# Sensor_Module_0x04_Luminosity_TSL2561_v2.net
KiCad netlist of a schematic drawn in EAGLE
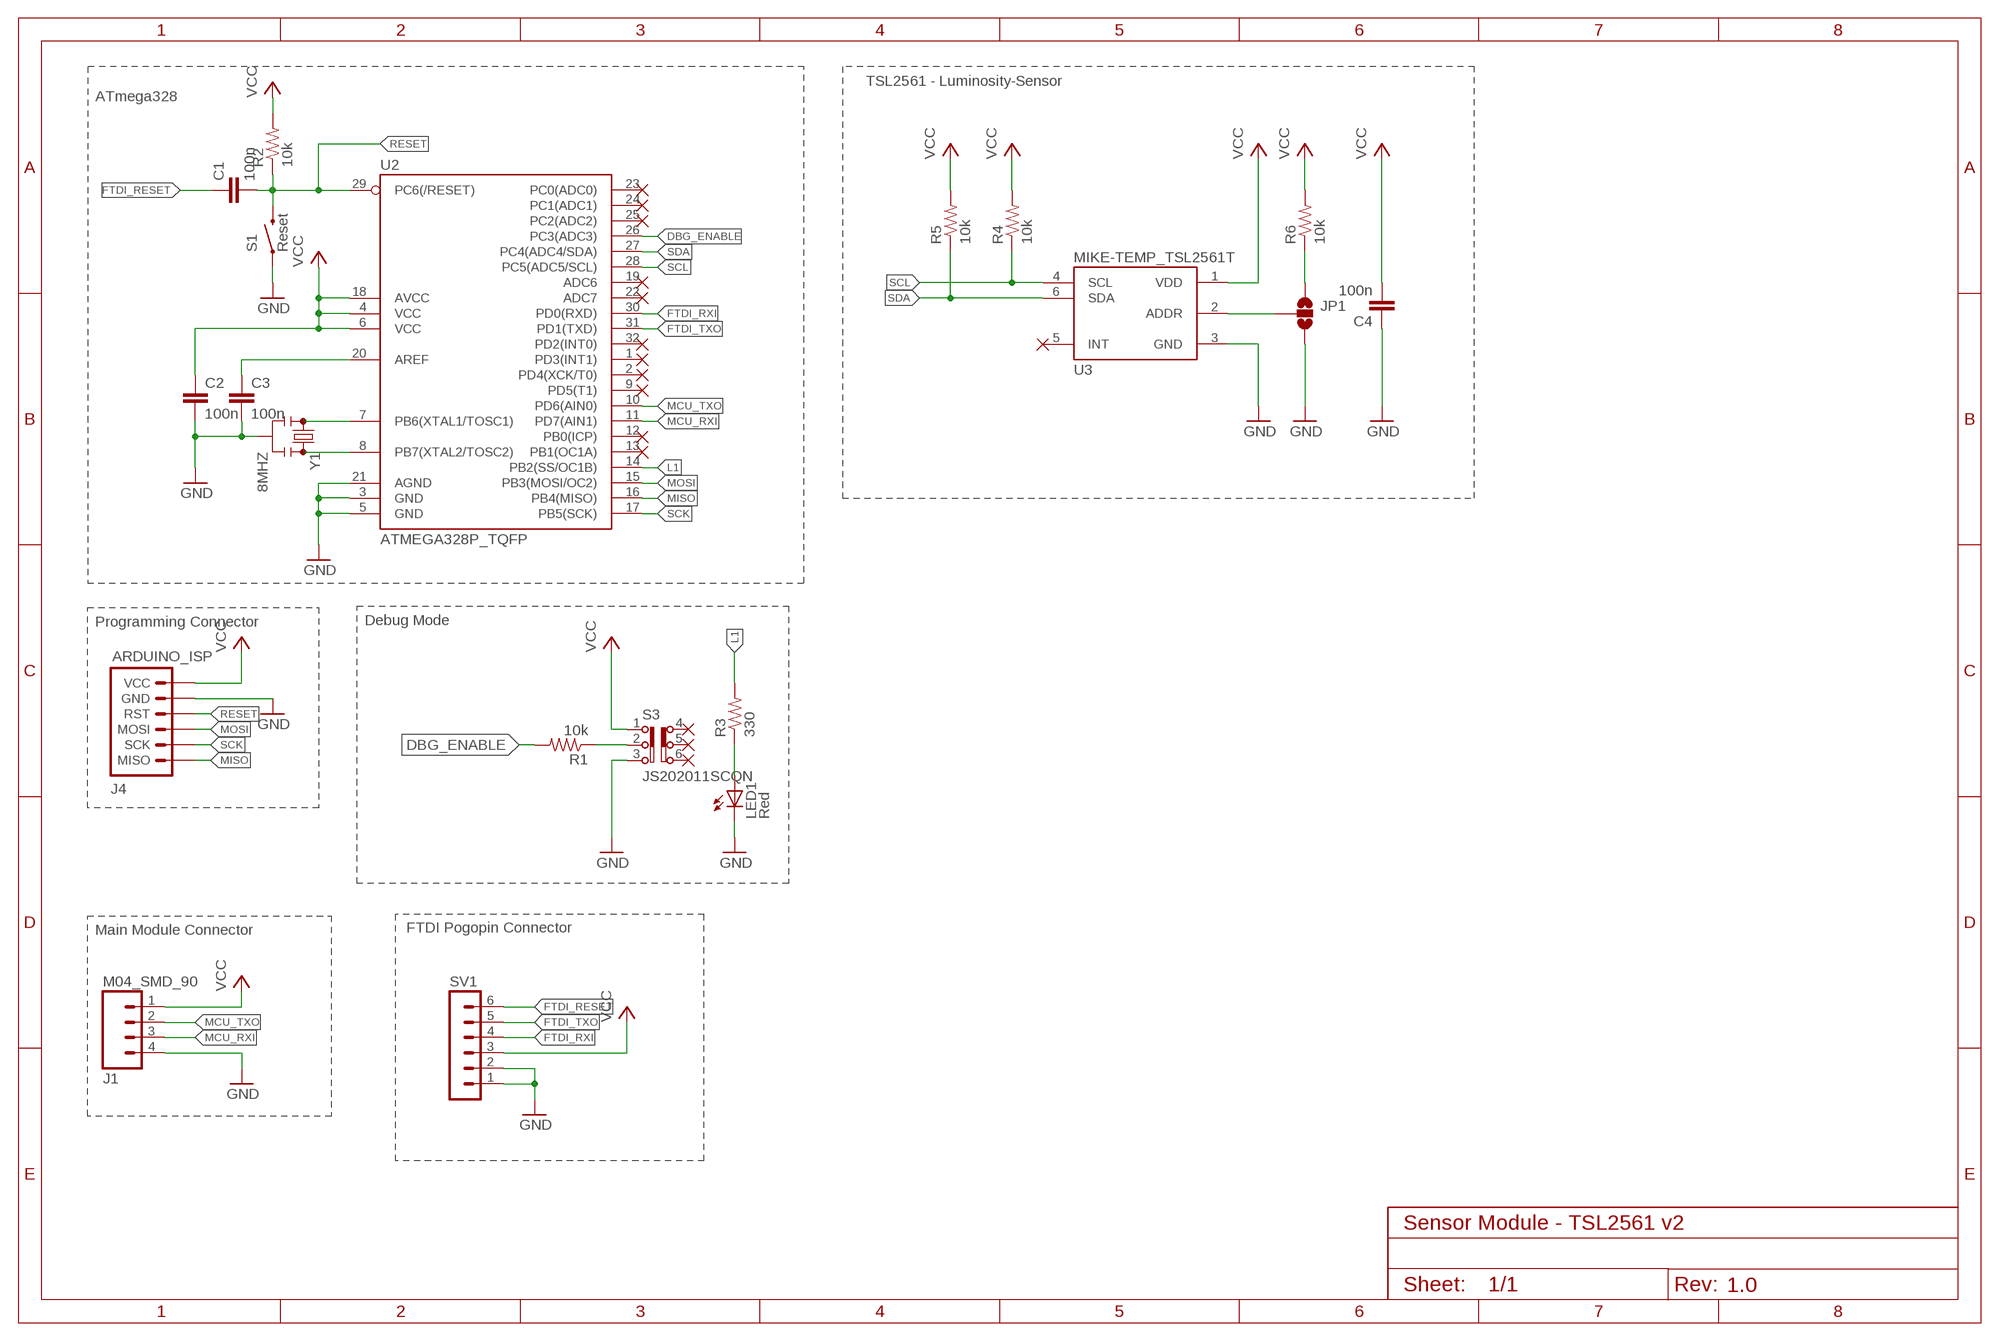
[diagram p0: schematic, sheet 1]

(export (version "E")
  (design (tool "Eeschema 10.0.6"))
  (components
    (comp (ref "C1")
      (value "100n")
      (footprint "eagle-import:C0805")
      (libsource (lib "eagle-import") (part "C"))
    )
    (comp (ref "C2")
      (value "100n")
      (footprint "eagle-import:C0805")
      (libsource (lib "eagle-import") (part "C"))
    )
    (comp (ref "C3")
      (value "100n")
      (footprint "eagle-import:C0805")
      (libsource (lib "eagle-import") (part "C"))
    )
    (comp (ref "C4")
      (value "100n")
      (footprint "eagle-import:C0805")
      (libsource (lib "eagle-import") (part "C"))
    )
    (comp (ref "J1")
      (value "M04_SMD_90")
      (footprint "eagle-import:M04_SMD_90")
      (libsource (lib "eagle-import") (part "M04_SMD_90"))
    )
    (comp (ref "J4")
      (value "ARDUINO_ISP")
      (footprint "eagle-import:M-2X3")
      (libsource (lib "eagle-import") (part "ARDUINO_ISP"))
    )
    (comp (ref "JP1")
      (value "MIKE-TEMP_SOLDERJUMPER_2WAYS")
      (footprint "eagle-import:MIKE-TEMP_SJ_3")
      (libsource (lib "eagle-import") (part "MIKE-TEMP_SOLDERJUMPER_2WAYS"))
    )
    (comp (ref "LED1")
      (value "Red")
      (footprint "eagle-import:SML0805")
      (libsource (lib "eagle-import") (part "LEDSML0805"))
    )
    (comp (ref "R1")
      (value "10k")
      (footprint "eagle-import:0805")
      (libsource (lib "eagle-import") (part "RESISTOR0805-RES"))
    )
    (comp (ref "R2")
      (value "10k")
      (footprint "eagle-import:0805")
      (libsource (lib "eagle-import") (part "RESISTOR0805-RES"))
    )
    (comp (ref "R3")
      (value "330")
      (footprint "eagle-import:0805")
      (libsource (lib "eagle-import") (part "RESISTOR0805-RES"))
    )
    (comp (ref "R4")
      (value "10k")
      (footprint "eagle-import:0805")
      (libsource (lib "eagle-import") (part "RESISTOR0805-RES"))
    )
    (comp (ref "R5")
      (value "10k")
      (footprint "eagle-import:0805")
      (libsource (lib "eagle-import") (part "RESISTOR0805-RES"))
    )
    (comp (ref "R6")
      (value "10k")
      (footprint "eagle-import:0805")
      (libsource (lib "eagle-import") (part "RESISTOR0805-RES"))
    )
    (comp (ref "S1")
      (value "Reset")
      (footprint "eagle-import:M-PUSHBUTTON-SMD")
      (libsource (lib "eagle-import") (part "PUSHBUTTON"))
    )
    (comp (ref "S3")
      (value "JS202011SCQN")
      (footprint "eagle-import:JS202011SCQN")
      (libsource (lib "eagle-import") (part "JS202011SCQN"))
    )
    (comp (ref "SV1")
      (value "MA06-1")
      (footprint "eagle-import:MA06-1")
      (libsource (lib "eagle-import") (part "MA06-1"))
    )
    (comp (ref "U2")
      (value "ATMEGA328P_TQFP")
      (footprint "eagle-import:TQFP32-08")
      (libsource (lib "eagle-import") (part "ATMEGA328P_TQFP"))
    )
    (comp (ref "U3")
      (value "MIKE-TEMP_TSL2561T")
      (footprint "eagle-import:MIKE-TEMP_TMB-6")
      (libsource (lib "eagle-import") (part "MIKE-TEMP_TSL2561T"))
    )
    (comp (ref "Y1")
      (value "8MHZ")
      (footprint "eagle-import:RESONATOR-SMD")
      (libsource (lib "eagle-import") (part "RESONATOR8MHZ"))
    )
  )
  (nets
    (net (code "1") (name "DBG_ENABLE") (class "Default")
      (node (ref "R1") (pin "2") (pinfunction "2_2") (pintype "passive"))
      (node (ref "U2") (pin "26") (pinfunction "PC3(ADC3)_26") (pintype "bidirectional"))
    )
    (net (code "2") (name "FTDI_RESET") (class "Default")
      (node (ref "C1") (pin "1") (pinfunction "1_1") (pintype "passive"))
      (node (ref "SV1") (pin "6") (pinfunction "6_6") (pintype "passive"))
    )
    (net (code "3") (name "FTDI_RXI") (class "Default")
      (node (ref "SV1") (pin "4") (pinfunction "4_4") (pintype "passive"))
      (node (ref "U2") (pin "30") (pinfunction "PD0(RXD)_30") (pintype "bidirectional"))
    )
    (net (code "4") (name "FTDI_TXO") (class "Default")
      (node (ref "SV1") (pin "5") (pinfunction "5_5") (pintype "passive"))
      (node (ref "U2") (pin "31") (pinfunction "PD1(TXD)_31") (pintype "bidirectional"))
    )
    (net (code "5") (name "GND") (class "Default")
      (node (ref "C2") (pin "2") (pinfunction "2_2") (pintype "passive"))
      (node (ref "C3") (pin "2") (pinfunction "2_2") (pintype "passive"))
      (node (ref "C4") (pin "1") (pinfunction "1_1") (pintype "passive"))
      (node (ref "J1") (pin "4") (pinfunction "4_4") (pintype "passive"))
      (node (ref "J4") (pin "P$5") (pinfunction "GND_P$5") (pintype "passive"))
      (node (ref "JP1") (pin "3") (pinfunction "3_3") (pintype "passive"))
      (node (ref "LED1") (pin "C") (pinfunction "C_C") (pintype "passive"))
      (node (ref "S1") (pin "1") (pinfunction "LEFT_1") (pintype "passive"))
      (node (ref "S1") (pin "2") (pinfunction "LEFT_2") (pintype "passive"))
      (node (ref "S3") (pin "3") (pinfunction "3_3") (pintype "passive"))
      (node (ref "SV1") (pin "1") (pinfunction "1_1") (pintype "passive"))
      (node (ref "SV1") (pin "2") (pinfunction "2_2") (pintype "passive"))
      (node (ref "U2") (pin "21") (pinfunction "AGND_21") (pintype "bidirectional"))
      (node (ref "U2") (pin "3") (pinfunction "GND_3") (pintype "bidirectional"))
      (node (ref "U2") (pin "5") (pinfunction "GND_5") (pintype "bidirectional"))
      (node (ref "U3") (pin "3") (pinfunction "GND_3") (pintype "power_in"))
      (node (ref "Y1") (pin "2") (pinfunction "2_2") (pintype "passive"))
    )
    (net (code "6") (name "L1") (class "Default")
      (node (ref "R3") (pin "2") (pinfunction "2_2") (pintype "passive"))
      (node (ref "U2") (pin "14") (pinfunction "PB2(SS/OC1B)_14") (pintype "bidirectional"))
    )
    (net (code "7") (name "MCU_RXI") (class "Default")
      (node (ref "J1") (pin "3") (pinfunction "3_3") (pintype "passive"))
      (node (ref "U2") (pin "11") (pinfunction "PD7(AIN1)_11") (pintype "bidirectional"))
    )
    (net (code "8") (name "MCU_TXO") (class "Default")
      (node (ref "J1") (pin "2") (pinfunction "2_2") (pintype "passive"))
      (node (ref "U2") (pin "10") (pinfunction "PD6(AIN0)_10") (pintype "bidirectional"))
    )
    (net (code "9") (name "MISO") (class "Default")
      (node (ref "J4") (pin "P$1") (pinfunction "MISO_P$1") (pintype "passive"))
      (node (ref "U2") (pin "16") (pinfunction "PB4(MISO)_16") (pintype "bidirectional"))
    )
    (net (code "10") (name "MOSI") (class "Default")
      (node (ref "J4") (pin "P$3") (pinfunction "MOSI_P$3") (pintype "passive"))
      (node (ref "U2") (pin "15") (pinfunction "PB3(MOSI/OC2)_15") (pintype "bidirectional"))
    )
    (net (code "11") (name "Net-(JP1-Pad1)") (class "Default")
      (node (ref "JP1") (pin "1") (pinfunction "1_1") (pintype "passive"))
      (node (ref "R6") (pin "1") (pinfunction "1_1") (pintype "passive"))
    )
    (net (code "12") (name "Net-(LED1-PadA)") (class "Default")
      (node (ref "LED1") (pin "A") (pinfunction "A_A") (pintype "passive"))
      (node (ref "R3") (pin "1") (pinfunction "1_1") (pintype "passive"))
    )
    (net (code "13") (name "Net-(R1-Pad1)") (class "Default")
      (node (ref "R1") (pin "1") (pinfunction "1_1") (pintype "passive"))
      (node (ref "S3") (pin "2") (pinfunction "2_2") (pintype "passive"))
    )
    (net (code "14") (name "Net-(U2-AREF)") (class "Default")
      (node (ref "C3") (pin "1") (pinfunction "1_1") (pintype "passive"))
      (node (ref "U2") (pin "20") (pinfunction "AREF_20") (pintype "bidirectional"))
    )
    (net (code "15") (name "Net-(U2-PB6(XTAL1{slash}TOSC1))") (class "Default")
      (node (ref "U2") (pin "7") (pinfunction "PB6(XTAL1/TOSC1)_7") (pintype "bidirectional"))
      (node (ref "Y1") (pin "1") (pinfunction "1_1") (pintype "passive"))
    )
    (net (code "16") (name "Net-(U2-PB7(XTAL2{slash}TOSC2))") (class "Default")
      (node (ref "U2") (pin "8") (pinfunction "PB7(XTAL2/TOSC2)_8") (pintype "bidirectional"))
      (node (ref "Y1") (pin "3") (pinfunction "3_3") (pintype "passive"))
    )
    (net (code "17") (name "Net-(U3-ADDR)") (class "Default")
      (node (ref "JP1") (pin "2") (pinfunction "2_2") (pintype "passive"))
      (node (ref "U3") (pin "2") (pinfunction "ADDR_2") (pintype "input"))
    )
    (net (code "18") (name "RESET") (class "Default")
      (node (ref "C1") (pin "2") (pinfunction "2_2") (pintype "passive"))
      (node (ref "J4") (pin "P$4") (pinfunction "RST_P$4") (pintype "passive"))
      (node (ref "R2") (pin "1") (pinfunction "1_1") (pintype "passive"))
      (node (ref "S1") (pin "3") (pinfunction "RIGHT_3") (pintype "passive"))
      (node (ref "S1") (pin "4") (pinfunction "RIGHT_4") (pintype "passive"))
      (node (ref "U2") (pin "29") (pinfunction "PC6(/RESET)_29") (pintype "bidirectional"))
    )
    (net (code "19") (name "SCK") (class "Default")
      (node (ref "J4") (pin "P$2") (pinfunction "SCK_P$2") (pintype "passive"))
      (node (ref "U2") (pin "17") (pinfunction "PB5(SCK)_17") (pintype "bidirectional"))
    )
    (net (code "20") (name "SCL") (class "Default")
      (node (ref "R4") (pin "1") (pinfunction "1_1") (pintype "passive"))
      (node (ref "U2") (pin "28") (pinfunction "PC5(ADC5/SCL)_28") (pintype "bidirectional"))
      (node (ref "U3") (pin "4") (pinfunction "SCL_4") (pintype "input"))
    )
    (net (code "21") (name "SDA") (class "Default")
      (node (ref "R5") (pin "1") (pinfunction "1_1") (pintype "passive"))
      (node (ref "U2") (pin "27") (pinfunction "PC4(ADC4/SDA)_27") (pintype "bidirectional"))
      (node (ref "U3") (pin "6") (pinfunction "SDA_6") (pintype "bidirectional"))
    )
    (net (code "22") (name "VCC") (class "Default")
      (node (ref "C2") (pin "1") (pinfunction "1_1") (pintype "passive"))
      (node (ref "C4") (pin "2") (pinfunction "2_2") (pintype "passive"))
      (node (ref "J1") (pin "1") (pinfunction "1_1") (pintype "passive"))
      (node (ref "J4") (pin "P$6") (pinfunction "VCC_P$6") (pintype "passive"))
      (node (ref "R2") (pin "2") (pinfunction "2_2") (pintype "passive"))
      (node (ref "R4") (pin "2") (pinfunction "2_2") (pintype "passive"))
      (node (ref "R5") (pin "2") (pinfunction "2_2") (pintype "passive"))
      (node (ref "R6") (pin "2") (pinfunction "2_2") (pintype "passive"))
      (node (ref "S3") (pin "1") (pinfunction "1_1") (pintype "passive"))
      (node (ref "SV1") (pin "3") (pinfunction "3_3") (pintype "passive"))
      (node (ref "U2") (pin "18") (pinfunction "AVCC_18") (pintype "bidirectional"))
      (node (ref "U2") (pin "4") (pinfunction "VCC_4") (pintype "bidirectional"))
      (node (ref "U2") (pin "6") (pinfunction "VCC_6") (pintype "bidirectional"))
      (node (ref "U3") (pin "1") (pinfunction "VDD_1") (pintype "power_in"))
    )
    (net (code "23") (name "unconnected-(S3-Pad4)") (class "Default")
      (node (ref "S3") (pin "4") (pinfunction "4_4") (pintype "passive"))
    )
    (net (code "24") (name "unconnected-(S3-Pad5)") (class "Default")
      (node (ref "S3") (pin "5") (pinfunction "5_5") (pintype "passive"))
    )
    (net (code "25") (name "unconnected-(S3-Pad6)") (class "Default")
      (node (ref "S3") (pin "6") (pinfunction "6_6") (pintype "passive"))
    )
    (net (code "26") (name "unconnected-(U2-ADC6-Pad19)") (class "Default")
      (node (ref "U2") (pin "19") (pinfunction "ADC6_19") (pintype "bidirectional"))
    )
    (net (code "27") (name "unconnected-(U2-ADC7-Pad22)") (class "Default")
      (node (ref "U2") (pin "22") (pinfunction "ADC7_22") (pintype "bidirectional"))
    )
    (net (code "28") (name "unconnected-(U2-PB0(ICP)-Pad12)") (class "Default")
      (node (ref "U2") (pin "12") (pinfunction "PB0(ICP)_12") (pintype "bidirectional"))
    )
    (net (code "29") (name "unconnected-(U2-PB1(OC1A)-Pad13)") (class "Default")
      (node (ref "U2") (pin "13") (pinfunction "PB1(OC1A)_13") (pintype "bidirectional"))
    )
    (net (code "30") (name "unconnected-(U2-PC0(ADC0)-Pad23)") (class "Default")
      (node (ref "U2") (pin "23") (pinfunction "PC0(ADC0)_23") (pintype "bidirectional"))
    )
    (net (code "31") (name "unconnected-(U2-PC1(ADC1)-Pad24)") (class "Default")
      (node (ref "U2") (pin "24") (pinfunction "PC1(ADC1)_24") (pintype "bidirectional"))
    )
    (net (code "32") (name "unconnected-(U2-PC2(ADC2)-Pad25)") (class "Default")
      (node (ref "U2") (pin "25") (pinfunction "PC2(ADC2)_25") (pintype "bidirectional"))
    )
    (net (code "33") (name "unconnected-(U2-PD2(INT0)-Pad32)") (class "Default")
      (node (ref "U2") (pin "32") (pinfunction "PD2(INT0)_32") (pintype "bidirectional"))
    )
    (net (code "34") (name "unconnected-(U2-PD3(INT1)-Pad1)") (class "Default")
      (node (ref "U2") (pin "1") (pinfunction "PD3(INT1)_1") (pintype "bidirectional"))
    )
    (net (code "35") (name "unconnected-(U2-PD4(XCK{slash}T0)-Pad2)") (class "Default")
      (node (ref "U2") (pin "2") (pinfunction "PD4(XCK/T0)_2") (pintype "bidirectional"))
    )
    (net (code "36") (name "unconnected-(U2-PD5(T1)-Pad9)") (class "Default")
      (node (ref "U2") (pin "9") (pinfunction "PD5(T1)_9") (pintype "bidirectional"))
    )
    (net (code "37") (name "unconnected-(U3-INT-Pad5)") (class "Default")
      (node (ref "U3") (pin "5") (pinfunction "INT_5") (pintype "output"))
    )
  )
)
